# Power_Regulation.net
KiCad netlist of a schematic drawn in Altium Designer
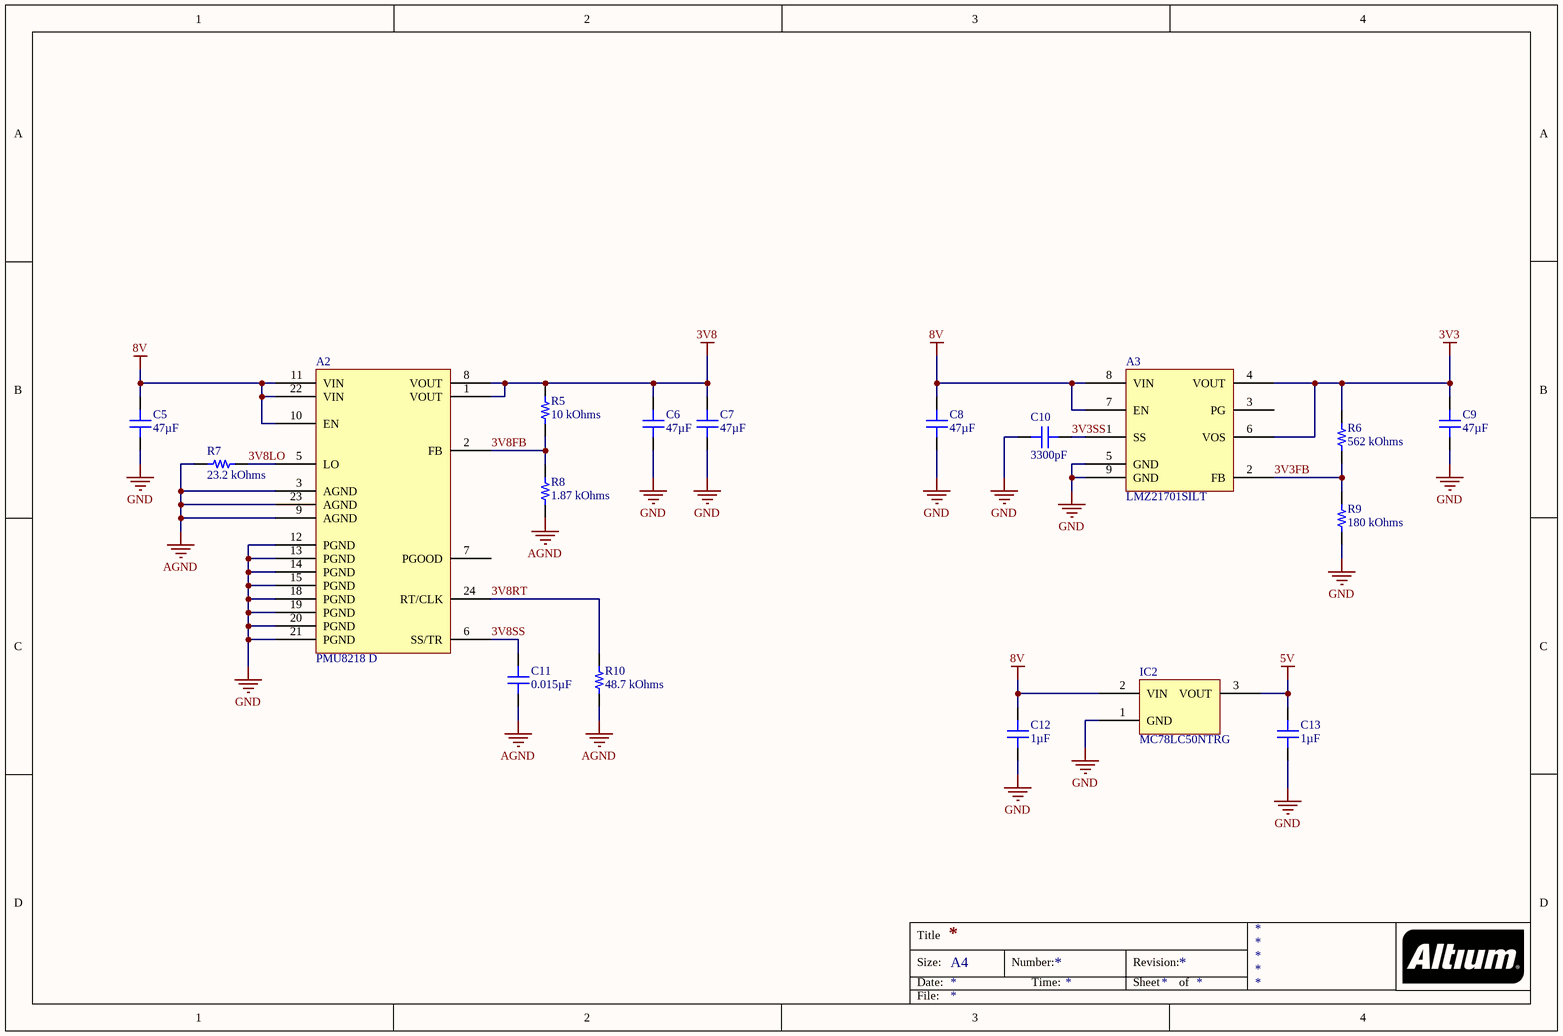
[diagram p0: Power Regulation.SchDoc]

(export (version "E")
  (design (tool "Eeschema 10.0.6"))
  (components
    (comp (ref "A2")
      (value "PMU8218 D")
      (footprint "FLEX QFM-24 MOL")
      (description "ANALOG POL; 4.5-17VIN; 0.6-5.5VO")
      (fields (field (name "MANUFACTURER") "Flex Power Modules"))
      (libsource (lib "Celestial Altium Library - altium_library") (part "FLEX PMU 8000"))
    )
    (comp (ref "A3")
      (value "LMZ21701SILT")
      (footprint "TI MICROSIP-8 SIL0008E")
      (description "DC DC CONVERTER 0.9-6V 6W")
      (fields (field (name "MANUFACTURER") "Texas Instruments"))
      (libsource (lib "Celestial Altium Library - altium_library") (part "TI LMZ21701"))
    )
    (comp (ref "C5")
      (value "47µF")
      (footprint "CAP 1210_3225 - 2.8MM")
      (description "CAP CER 47UF 10V X7R 1210")
      (fields (field (name "PART NUMBER") "LMK325B7476MM-PR") (field (name "MANUFACTURER") "Taiyo Yuden"))
      (libsource (lib "Celestial Altium Library - altium_library") (part "Capacitor"))
    )
    (comp (ref "C6")
      (value "47µF")
      (footprint "CAP 1210_3225 - 2.8MM")
      (description "CAP CER 47UF 10V X7R 1210")
      (fields (field (name "PART NUMBER") "LMK325B7476MM-PR") (field (name "MANUFACTURER") "Taiyo Yuden"))
      (libsource (lib "Celestial Altium Library - altium_library") (part "Capacitor"))
    )
    (comp (ref "C7")
      (value "47µF")
      (footprint "CAP 1210_3225 - 2.8MM")
      (description "CAP CER 47UF 10V X7R 1210")
      (fields (field (name "PART NUMBER") "LMK325B7476MM-PR") (field (name "MANUFACTURER") "Taiyo Yuden"))
      (libsource (lib "Celestial Altium Library - altium_library") (part "Capacitor"))
    )
    (comp (ref "C8")
      (value "47µF")
      (footprint "CAP 1210_3225 - 2.8MM")
      (description "CAP CER 47UF 10V X7R 1210")
      (fields (field (name "PART NUMBER") "LMK325B7476MM-PR") (field (name "MANUFACTURER") "Taiyo Yuden"))
      (libsource (lib "Celestial Altium Library - altium_library") (part "Capacitor"))
    )
    (comp (ref "C9")
      (value "47µF")
      (footprint "CAP 1210_3225 - 2.8MM")
      (description "CAP CER 47UF 10V X7R 1210")
      (fields (field (name "PART NUMBER") "LMK325B7476MM-PR") (field (name "MANUFACTURER") "Taiyo Yuden"))
      (libsource (lib "Celestial Altium Library - altium_library") (part "Capacitor"))
    )
    (comp (ref "C10")
      (value "3300pF")
      (footprint "CAP 0201_0603")
      (description "CAP CER 3300PF 6.3V X7R 0201")
      (fields
        (field (name "PART NUMBER") "GRM033R70J332KA01D")
        (field (name "MANUFACTURER") "Murata Electronics")
      )
      (libsource (lib "Celestial Altium Library - altium_library") (part "Capacitor"))
    )
    (comp (ref "C11")
      (value "0.015µF")
      (footprint "CAP 0201_0603")
      (description "CAP CER 0.015UF 6.3V X5R 0201")
      (fields (field (name "PART NUMBER") "CC0201KRX5R5BB153") (field (name "MANUFACTURER") "Yageo"))
      (libsource (lib "Celestial Altium Library - altium_library") (part "Capacitor"))
    )
    (comp (ref "C12")
      (value "1µF")
      (footprint "CAP 0402_1005")
      (description "CAP CER 1UF 16V X5R 0402")
      (fields
        (field (name "PART NUMBER") "GRM155R61C105MA12D")
        (field (name "MANUFACTURER") "Murata Electronics")
      )
      (libsource (lib "Celestial Altium Library - altium_library") (part "Capacitor"))
    )
    (comp (ref "C13")
      (value "1µF")
      (footprint "CAP 0402_1005")
      (description "CAP CER 1UF 16V X5R 0402")
      (fields
        (field (name "PART NUMBER") "GRM155R61C105MA12D")
        (field (name "MANUFACTURER") "Murata Electronics")
      )
      (libsource (lib "Celestial Altium Library - altium_library") (part "Capacitor"))
    )
    (comp (ref "IC2")
      (value "MC78LC50NTRG")
      (footprint "ON SEMI TSOT-23-5 419AE")
      (description "IC REG LINEAR 5V 100MA 5TSOP")
      (fields (field (name "MANUFACTURER") "ON Semiconductor"))
      (libsource (lib "Celestial Altium Library - altium_library") (part "ON Semi MC78LC00"))
    )
    (comp (ref "R5")
      (value "10 kOhms")
      (footprint "RES 0201_0603")
      (description "RES SMD 10K OHM 1% 1/20W 0201")
      (fields
        (field (name "PART NUMBER") "ERJ-1GNF1002C")
        (field (name "MANUFACTURER") "Panasonic Electronic Components")
      )
      (libsource (lib "Celestial Altium Library - altium_library") (part "Resistor"))
    )
    (comp (ref "R6")
      (value "562 kOhms")
      (footprint "RES 0201_0603")
      (description "RES SMD 562K OHM 1% 1/20W 0201")
      (fields
        (field (name "PART NUMBER") "ERJ-1GNF5623C")
        (field (name "MANUFACTURER") "Panasonic Electronic Components")
      )
      (libsource (lib "Celestial Altium Library - altium_library") (part "Resistor"))
    )
    (comp (ref "R7")
      (value "23.2 kOhms")
      (footprint "RES 0201_0603")
      (description "RES SMD 23.2K OHM 1% 1/20W 0201")
      (fields
        (field (name "PART NUMBER") "ERJ-1GNF2322C")
        (field (name "MANUFACTURER") "Panasonic Electronic Components")
      )
      (libsource (lib "Celestial Altium Library - altium_library") (part "Resistor"))
    )
    (comp (ref "R8")
      (value "1.87 kOhms")
      (footprint "RES 0201_0603")
      (description "RES SMD 1.87K OHM 1% 1/20W 0201")
      (fields
        (field (name "PART NUMBER") "ERJ-1GNF1871C")
        (field (name "MANUFACTURER") "Panasonic Electronic Components")
      )
      (libsource (lib "Celestial Altium Library - altium_library") (part "Resistor"))
    )
    (comp (ref "R9")
      (value "180 kOhms")
      (footprint "RES 0201_0603")
      (description "RES SMD 180K OHM 1% 1/20W 0201")
      (fields
        (field (name "PART NUMBER") "ERJ-1GNF1803C")
        (field (name "MANUFACTURER") "Panasonic Electronic Components")
      )
      (libsource (lib "Celestial Altium Library - altium_library") (part "Resistor"))
    )
    (comp (ref "R10")
      (value "48.7 kOhms")
      (footprint "RES 0201_0603")
      (description "RES SMD 48.7K OHM 1% 1/20W 0201")
      (fields
        (field (name "PART NUMBER") "ERJ-1GNF4872C")
        (field (name "MANUFACTURER") "Panasonic Electronic Components")
      )
      (libsource (lib "Celestial Altium Library - altium_library") (part "Resistor"))
    )
  )
  (nets
    (net (code "1") (name "/3V3FB") (class "Default")
      (node (ref "A3") (pin "2") (pinfunction "FB_2") (pintype "passive"))
      (node (ref "R6") (pin "1") (pinfunction "1_1") (pintype "passive"))
      (node (ref "R9") (pin "2") (pinfunction "2_2") (pintype "passive"))
    )
    (net (code "2") (name "/3V3SS") (class "Default")
      (node (ref "A3") (pin "1") (pinfunction "SS_1") (pintype "passive"))
      (node (ref "C10") (pin "2") (pinfunction "2_2") (pintype "passive"))
    )
    (net (code "3") (name "/3V8FB") (class "Default")
      (node (ref "A2") (pin "2") (pinfunction "FB_2") (pintype "passive"))
      (node (ref "R5") (pin "1") (pinfunction "1_1") (pintype "passive"))
      (node (ref "R8") (pin "2") (pinfunction "2_2") (pintype "passive"))
    )
    (net (code "4") (name "/3V8LO") (class "Default")
      (node (ref "A2") (pin "5") (pinfunction "LO_5") (pintype "passive"))
      (node (ref "R7") (pin "2") (pinfunction "2_2") (pintype "passive"))
    )
    (net (code "5") (name "/3V8RT") (class "Default")
      (node (ref "A2") (pin "24") (pinfunction "RT/CLK_24") (pintype "passive"))
      (node (ref "R10") (pin "2") (pinfunction "2_2") (pintype "passive"))
    )
    (net (code "6") (name "/3V8SS") (class "Default")
      (node (ref "A2") (pin "6") (pinfunction "SS/TR_6") (pintype "passive"))
      (node (ref "C11") (pin "2") (pinfunction "2_2") (pintype "passive"))
    )
    (net (code "7") (name "3V3") (class "Default")
      (node (ref "A3") (pin "4") (pinfunction "VOUT_4") (pintype "passive"))
      (node (ref "A3") (pin "6") (pinfunction "VOS_6") (pintype "passive"))
      (node (ref "C9") (pin "2") (pinfunction "2_2") (pintype "passive"))
      (node (ref "R6") (pin "2") (pinfunction "2_2") (pintype "passive"))
    )
    (net (code "8") (name "3V8") (class "Default")
      (node (ref "A2") (pin "1") (pinfunction "VOUT_1") (pintype "passive"))
      (node (ref "A2") (pin "8") (pinfunction "VOUT_8") (pintype "passive"))
      (node (ref "C6") (pin "2") (pinfunction "2_2") (pintype "passive"))
      (node (ref "C7") (pin "2") (pinfunction "2_2") (pintype "passive"))
      (node (ref "R5") (pin "2") (pinfunction "2_2") (pintype "passive"))
    )
    (net (code "9") (name "5V") (class "Default")
      (node (ref "C13") (pin "2") (pinfunction "2_2") (pintype "passive"))
      (node (ref "IC2") (pin "3") (pinfunction "VOUT_3") (pintype "passive"))
    )
    (net (code "10") (name "8V") (class "Default")
      (node (ref "A2") (pin "10") (pinfunction "EN_10") (pintype "passive"))
      (node (ref "A2") (pin "11") (pinfunction "VIN_11") (pintype "passive"))
      (node (ref "A2") (pin "22") (pinfunction "VIN_22") (pintype "passive"))
      (node (ref "A3") (pin "7") (pinfunction "EN_7") (pintype "passive"))
      (node (ref "A3") (pin "8") (pinfunction "VIN_8") (pintype "passive"))
      (node (ref "C12") (pin "2") (pinfunction "2_2") (pintype "passive"))
      (node (ref "C5") (pin "2") (pinfunction "2_2") (pintype "passive"))
      (node (ref "C8") (pin "2") (pinfunction "2_2") (pintype "passive"))
      (node (ref "IC2") (pin "2") (pinfunction "VIN_2") (pintype "passive"))
    )
    (net (code "11") (name "AGND") (class "Default")
      (node (ref "A2") (pin "23") (pinfunction "AGND_23") (pintype "passive"))
      (node (ref "A2") (pin "3") (pinfunction "AGND_3") (pintype "passive"))
      (node (ref "A2") (pin "9") (pinfunction "AGND_9") (pintype "passive"))
      (node (ref "C11") (pin "1") (pinfunction "1_1") (pintype "passive"))
      (node (ref "R10") (pin "1") (pinfunction "1_1") (pintype "passive"))
      (node (ref "R7") (pin "1") (pinfunction "1_1") (pintype "passive"))
      (node (ref "R8") (pin "1") (pinfunction "1_1") (pintype "passive"))
    )
    (net (code "12") (name "GND") (class "Default")
      (node (ref "A2") (pin "12") (pinfunction "PGND_12") (pintype "passive"))
      (node (ref "A2") (pin "13") (pinfunction "PGND_13") (pintype "passive"))
      (node (ref "A2") (pin "14") (pinfunction "PGND_14") (pintype "passive"))
      (node (ref "A2") (pin "15") (pinfunction "PGND_15") (pintype "passive"))
      (node (ref "A2") (pin "18") (pinfunction "PGND_18") (pintype "passive"))
      (node (ref "A2") (pin "19") (pinfunction "PGND_19") (pintype "passive"))
      (node (ref "A2") (pin "20") (pinfunction "PGND_20") (pintype "passive"))
      (node (ref "A2") (pin "21") (pinfunction "PGND_21") (pintype "passive"))
      (node (ref "A3") (pin "5") (pinfunction "GND_5") (pintype "passive"))
      (node (ref "A3") (pin "9") (pinfunction "GND_9") (pintype "passive"))
      (node (ref "C10") (pin "1") (pinfunction "1_1") (pintype "passive"))
      (node (ref "C12") (pin "1") (pinfunction "1_1") (pintype "passive"))
      (node (ref "C13") (pin "1") (pinfunction "1_1") (pintype "passive"))
      (node (ref "C5") (pin "1") (pinfunction "1_1") (pintype "passive"))
      (node (ref "C6") (pin "1") (pinfunction "1_1") (pintype "passive"))
      (node (ref "C7") (pin "1") (pinfunction "1_1") (pintype "passive"))
      (node (ref "C8") (pin "1") (pinfunction "1_1") (pintype "passive"))
      (node (ref "C9") (pin "1") (pinfunction "1_1") (pintype "passive"))
      (node (ref "IC2") (pin "1") (pinfunction "GND_1") (pintype "passive"))
      (node (ref "R9") (pin "1") (pinfunction "1_1") (pintype "passive"))
    )
    (net (code "13") (name "unconnected-(A2-PGOOD-Pad7)") (class "Default")
      (node (ref "A2") (pin "7") (pinfunction "PGOOD_7") (pintype "passive"))
    )
    (net (code "14") (name "unconnected-(A3-PG-Pad3)") (class "Default")
      (node (ref "A3") (pin "3") (pinfunction "PG_3") (pintype "passive"))
    )
  )
)
